# controller_8266_psu.net
KiCad netlist of a schematic drawn in Altium Designer
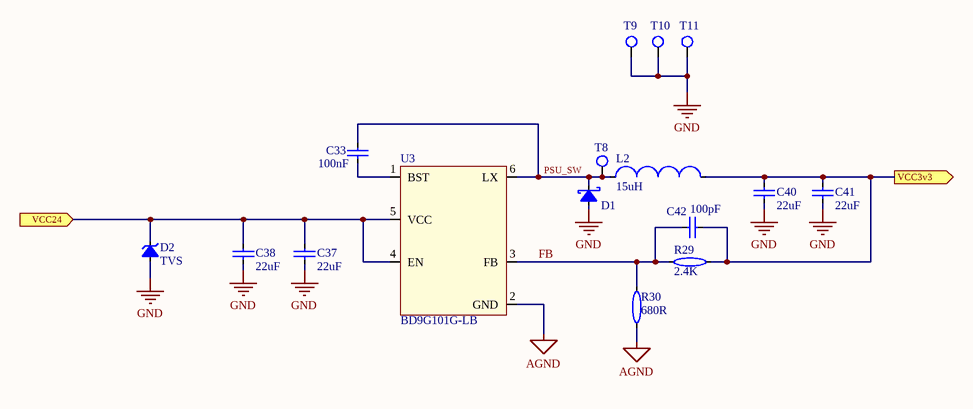
[diagram p0: controller_8266_psu.SchDoc]

(export (version "E")
  (design (tool "Eeschema 10.0.6"))
  (components
    (comp (ref "C33")
      (value "100nF")
      (footprint "CAPC_0603_1608X08L")
      (description "Capacitor")
      (fields (field (name "Comment") "Cap") (field (name "PUBLISHER") "Altium Limited"))
      (libsource (lib "controller_8266") (part "Cap"))
    )
    (comp (ref "C37")
      (value "22uF")
      (footprint "CAPC_1206_3216X16L")
      (description "Capacitor")
      (fields (field (name "Comment") "Cap") (field (name "PUBLISHER") "Altium Limited"))
      (libsource (lib "controller_8266") (part "Cap"))
    )
    (comp (ref "C38")
      (value "22uF")
      (footprint "CAPC_1206_3216X16L")
      (description "Capacitor")
      (fields (field (name "Comment") "Cap") (field (name "PUBLISHER") "Altium Limited"))
      (libsource (lib "controller_8266") (part "Cap"))
    )
    (comp (ref "C40")
      (value "22uF")
      (footprint "CAPC_1206_3216X16L")
      (description "Capacitor")
      (fields (field (name "Comment") "Cap") (field (name "PUBLISHER") "Altium Limited"))
      (libsource (lib "controller_8266") (part "Cap"))
    )
    (comp (ref "C41")
      (value "22uF")
      (footprint "CAPC_1206_3216X16L")
      (description "Capacitor")
      (fields (field (name "Comment") "Cap") (field (name "PUBLISHER") "Altium Limited"))
      (libsource (lib "controller_8266") (part "Cap"))
    )
    (comp (ref "C42")
      (value "100pF")
      (footprint "CAPC_0603_1608X08L")
      (description "Capacitor")
      (fields (field (name "Comment") "Cap") (field (name "PUBLISHER") "Altium Limited"))
      (libsource (lib "controller_8266") (part "Cap"))
    )
    (comp (ref "D1")
      (value "Schottky 40V 3A")
      (footprint "SOD123")
      (description "Schottky Diode")
      (fields (field (name "PUBLISHER") "Altium Limited"))
      (libsource (lib "controller_8266") (part "D Schottky"))
    )
    (comp (ref "D2")
      (value "TVS")
      (footprint "SODFL350X120-2L")
      (description "Schottky Diode")
      (fields
        (field (name "MANUFACTURER PART NUMBER") "SMBJ24CA")
        (field (name "MANUFACTURER") "Littelfuse")
        (field (name "PUBLISHER") "Altium Limited")
      )
      (libsource (lib "controller_8266") (part "D Zener"))
    )
    (comp (ref "L2")
      (value "15uH")
      (footprint "INDP4949X30N")
      (description "Inductor")
      (fields (field (name "PUBLISHER") "Altium Limited"))
      (libsource (lib "controller_8266") (part "Inductor"))
    )
    (comp (ref "R29")
      (value "2.4K")
      (footprint "RESC_0603_1608X08L")
      (description "Resistor")
      (fields (field (name "Comment") "Res2") (field (name "PUBLISHER") "Altium Limited"))
      (libsource (lib "controller_8266") (part "Res2"))
    )
    (comp (ref "R30")
      (value "680R")
      (footprint "RESC_0603_1608X08L")
      (description "Resistor")
      (fields (field (name "Comment") "Res2") (field (name "PUBLISHER") "Altium Limited"))
      (libsource (lib "controller_8266") (part "Res2"))
    )
    (comp (ref "T8")
      (value "Testpoint")
      (footprint "TESTPOINT")
      (libsource (lib "controller_8266") (part "Testpoint"))
    )
    (comp (ref "T9")
      (value "Testpoint")
      (footprint "TESTPOINT")
      (libsource (lib "controller_8266") (part "Testpoint"))
    )
    (comp (ref "T10")
      (value "Testpoint")
      (footprint "TESTPOINT")
      (libsource (lib "controller_8266") (part "Testpoint"))
    )
    (comp (ref "T11")
      (value "Testpoint")
      (footprint "TESTPOINT")
      (libsource (lib "controller_8266") (part "Testpoint"))
    )
    (comp (ref "U3")
      (value "BD9G101G-LB")
      (footprint "TSOP95P280X125-6L")
      (libsource (lib "controller_8266") (part "BD9G102G-LB"))
    )
  )
  (nets
    (net (code "1") (name "/FB") (class "Default")
      (node (ref "C42") (pin "1") (pinfunction "1_1") (pintype "passive"))
      (node (ref "R29") (pin "2") (pinfunction "2_2") (pintype "passive"))
      (node (ref "R30") (pin "1") (pinfunction "1_1") (pintype "passive"))
      (node (ref "U3") (pin "3") (pinfunction "FB_3") (pintype "passive"))
    )
    (net (code "2") (name "/PSU_SW") (class "Default")
      (node (ref "C33") (pin "2") (pinfunction "2_2") (pintype "passive"))
      (node (ref "D1") (pin "2") (pinfunction "K_2") (pintype "passive"))
      (node (ref "L2") (pin "1") (pinfunction "1_1") (pintype "passive"))
      (node (ref "T8") (pin "1") (pinfunction "VOUT_1") (pintype "passive"))
      (node (ref "U3") (pin "6") (pinfunction "LX_6") (pintype "passive"))
    )
    (net (code "3") (name "/VCC3v3") (class "Default")
      (node (ref "C40") (pin "2") (pinfunction "2_2") (pintype "passive"))
      (node (ref "C41") (pin "2") (pinfunction "2_2") (pintype "passive"))
      (node (ref "C42") (pin "2") (pinfunction "2_2") (pintype "passive"))
      (node (ref "L2") (pin "2") (pinfunction "2_2") (pintype "passive"))
      (node (ref "R29") (pin "1") (pinfunction "1_1") (pintype "passive"))
    )
    (net (code "4") (name "/VCC24") (class "Default")
      (node (ref "C37") (pin "2") (pinfunction "2_2") (pintype "passive"))
      (node (ref "C38") (pin "2") (pinfunction "2_2") (pintype "passive"))
      (node (ref "D2") (pin "2") (pinfunction "K_2") (pintype "passive"))
      (node (ref "U3") (pin "4") (pinfunction "EN_4") (pintype "passive"))
      (node (ref "U3") (pin "5") (pinfunction "VCC_5") (pintype "passive"))
    )
    (net (code "5") (name "AGND") (class "Default")
      (node (ref "R30") (pin "2") (pinfunction "2_2") (pintype "passive"))
      (node (ref "U3") (pin "2") (pinfunction "GND_2") (pintype "passive"))
    )
    (net (code "6") (name "GND") (class "Default")
      (node (ref "C37") (pin "1") (pinfunction "1_1") (pintype "passive"))
      (node (ref "C38") (pin "1") (pinfunction "1_1") (pintype "passive"))
      (node (ref "C40") (pin "1") (pinfunction "1_1") (pintype "passive"))
      (node (ref "C41") (pin "1") (pinfunction "1_1") (pintype "passive"))
      (node (ref "D1") (pin "1") (pinfunction "A_1") (pintype "passive"))
      (node (ref "D2") (pin "1") (pinfunction "A_1") (pintype "passive"))
      (node (ref "T10") (pin "1") (pinfunction "VOUT_1") (pintype "passive"))
      (node (ref "T11") (pin "1") (pinfunction "VOUT_1") (pintype "passive"))
      (node (ref "T9") (pin "1") (pinfunction "VOUT_1") (pintype "passive"))
    )
    (net (code "7") (name "Net-(U3-BST)") (class "Default")
      (node (ref "C33") (pin "1") (pinfunction "1_1") (pintype "passive"))
      (node (ref "U3") (pin "1") (pinfunction "BST_1") (pintype "passive"))
    )
  )
)
